# Interface_-_Debug.net
KiCad netlist of a schematic drawn in Altium Designer
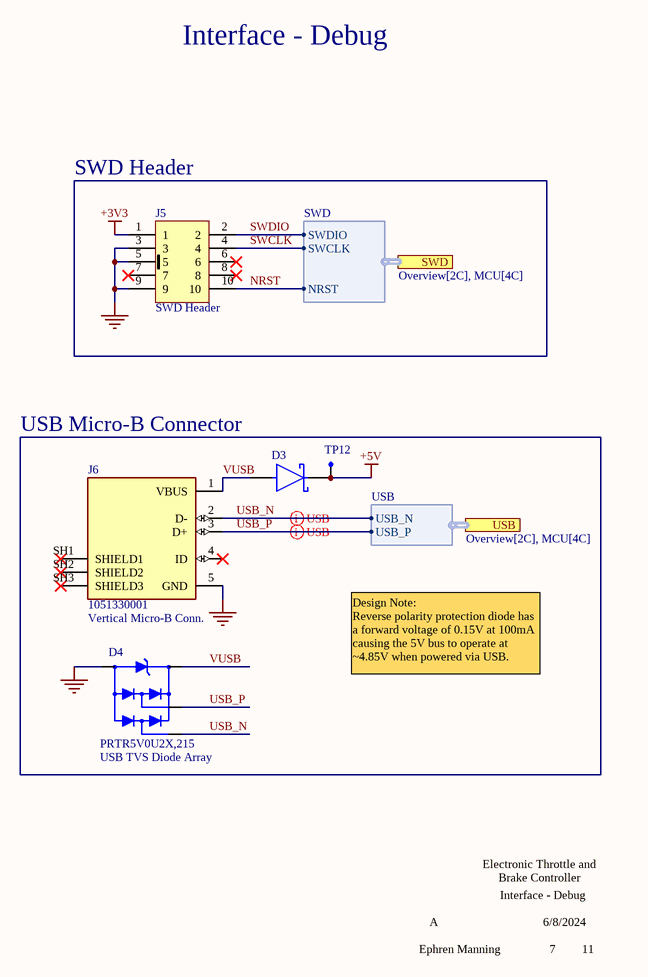
[diagram p0: Interface - Debug.SchDoc]

(export (version "E")
  (design (tool "Eeschema 10.0.6"))
  (components
    (comp (ref "D3")
      (value "LSM115JE3/TR13")
      (footprint "DIOM4336X33N")
      (description "15V 1A Schottky Diode, Very Low Forward Voltage")
      (fields (field (name "DIGIKEY PART NUMBER") "150-LSM115JE3/TR13CT-ND"))
      (libsource (lib "SAE @ UIC Formula Electric") (part "Schottky_Diode_Symbol"))
    )
    (comp (ref "D4")
      (value "PRTR5V0U2X,215")
      (footprint "SOT143B")
      (description "Diode Array, ESD")
      (fields (field (name "DIGIKEY PART NUMBER") "1727-3884-1-ND"))
      (libsource (lib "SAE @ UIC Formula Electric") (part "PRTR5V0U2X,215"))
    )
    (comp (ref "J5")
      (value "SWD Header")
      (footprint "FCI_20021111-00010T4LF")
      (description "SWD Unshrouded Connector")
      (fields (field (name "DIGIKEY PART NUMBER") "609-3712-ND"))
      (libsource (lib "SAE @ UIC Formula Electric") (part "20021111-00010T4LF"))
    )
    (comp (ref "J6")
      (value "1051330001")
      (footprint "MOLEX_1051330001")
      (description "Micro USB Type B 90 Degree Conn")
      (fields (field (name "DIGIKEY PART NUMBER") "WM9734CT-ND"))
      (libsource (lib "SAE @ UIC Formula Electric") (part "1051330001"))
    )
    (comp (ref "TP12")
      (value "SMD Testpoint")
      (footprint "SMD Testpoint-Footprint-1")
      (description "Flat 50x50mil Test Point")
      (libsource (lib "SAE @ UIC Formula Electric") (part "SMD Testpoint-Symbol-1"))
    )
  )
  (nets
    (net (code "3") (name "+3V3") (class "Default")
      (node (ref "J5") (pin "1") (pinfunction "1_1") (pintype "passive"))
    )
    (net (code "4") (name "+5V") (class "Default")
      (node (ref "D3") (pin "2") (pinfunction "2_2") (pintype "passive"))
      (node (ref "TP12") (pin "1") (pinfunction "1_1") (pintype "passive"))
    )
    (net (code "5") (name "/NRST") (class "Default")
      (node (ref "J5") (pin "10") (pinfunction "10_10") (pintype "passive"))
    )
    (net (code "6") (name "/SWCLK") (class "Default")
      (node (ref "J5") (pin "4") (pinfunction "4_4") (pintype "passive"))
    )
    (net (code "7") (name "/SWDIO") (class "Default")
      (node (ref "J5") (pin "2") (pinfunction "2_2") (pintype "passive"))
    )
    (net (code "8") (name "/USB_N") (class "Default")
      (node (ref "D4") (pin "3") (pinfunction "P$3_3") (pintype "passive"))
      (node (ref "J6") (pin "2") (pinfunction "D-_2") (pintype "bidirectional"))
    )
    (net (code "9") (name "/USB_P") (class "Default")
      (node (ref "D4") (pin "2") (pinfunction "P$2_2") (pintype "passive"))
      (node (ref "J6") (pin "3") (pinfunction "D+_3") (pintype "bidirectional"))
    )
    (net (code "10") (name "/VUSB") (class "Default")
      (node (ref "D3") (pin "1") (pinfunction "1_1") (pintype "passive"))
      (node (ref "D4") (pin "4") (pinfunction "P$4_4") (pintype "passive"))
      (node (ref "J6") (pin "1") (pinfunction "VBUS_1") (pintype "power_in"))
    )
    (net (code "13") (name "GND") (class "Default")
      (node (ref "D4") (pin "1") (pinfunction "P$1_1") (pintype "passive"))
      (node (ref "J5") (pin "3") (pinfunction "3_3") (pintype "passive"))
      (node (ref "J5") (pin "5") (pinfunction "5_5") (pintype "passive"))
      (node (ref "J5") (pin "9") (pinfunction "9_9") (pintype "passive"))
      (node (ref "J6") (pin "5") (pinfunction "GND_5") (pintype "power_in"))
    )
    (net (code "14") (name "unconnected-(J5-Pad6)") (class "Default")
      (node (ref "J5") (pin "6") (pinfunction "6_6") (pintype "passive+no_connect"))
    )
    (net (code "15") (name "unconnected-(J5-Pad7)") (class "Default")
      (node (ref "J5") (pin "7") (pinfunction "7_7") (pintype "passive+no_connect"))
    )
    (net (code "16") (name "unconnected-(J5-Pad8)") (class "Default")
      (node (ref "J5") (pin "8") (pinfunction "8_8") (pintype "passive+no_connect"))
    )
    (net (code "17") (name "unconnected-(J6-ID-Pad4)") (class "Default")
      (node (ref "J6") (pin "4") (pinfunction "ID_4") (pintype "bidirectional+no_connect"))
    )
    (net (code "18") (name "unconnected-(J6-SHIELD1-PadSH1)") (class "Default")
      (node (ref "J6") (pin "SH1") (pinfunction "SHIELD1_SH1") (pintype "passive+no_connect"))
    )
    (net (code "19") (name "unconnected-(J6-SHIELD2-PadSH2)") (class "Default")
      (node (ref "J6") (pin "SH2") (pinfunction "SHIELD2_SH2") (pintype "passive+no_connect"))
    )
    (net (code "20") (name "unconnected-(J6-SHIELD3-PadSH3)") (class "Default")
      (node (ref "J6") (pin "SH3") (pinfunction "SHIELD3_SH3") (pintype "passive+no_connect"))
    )
  )
)
